# gps_and_sensor_board.net
KiCad netlist of a schematic drawn in EAGLE
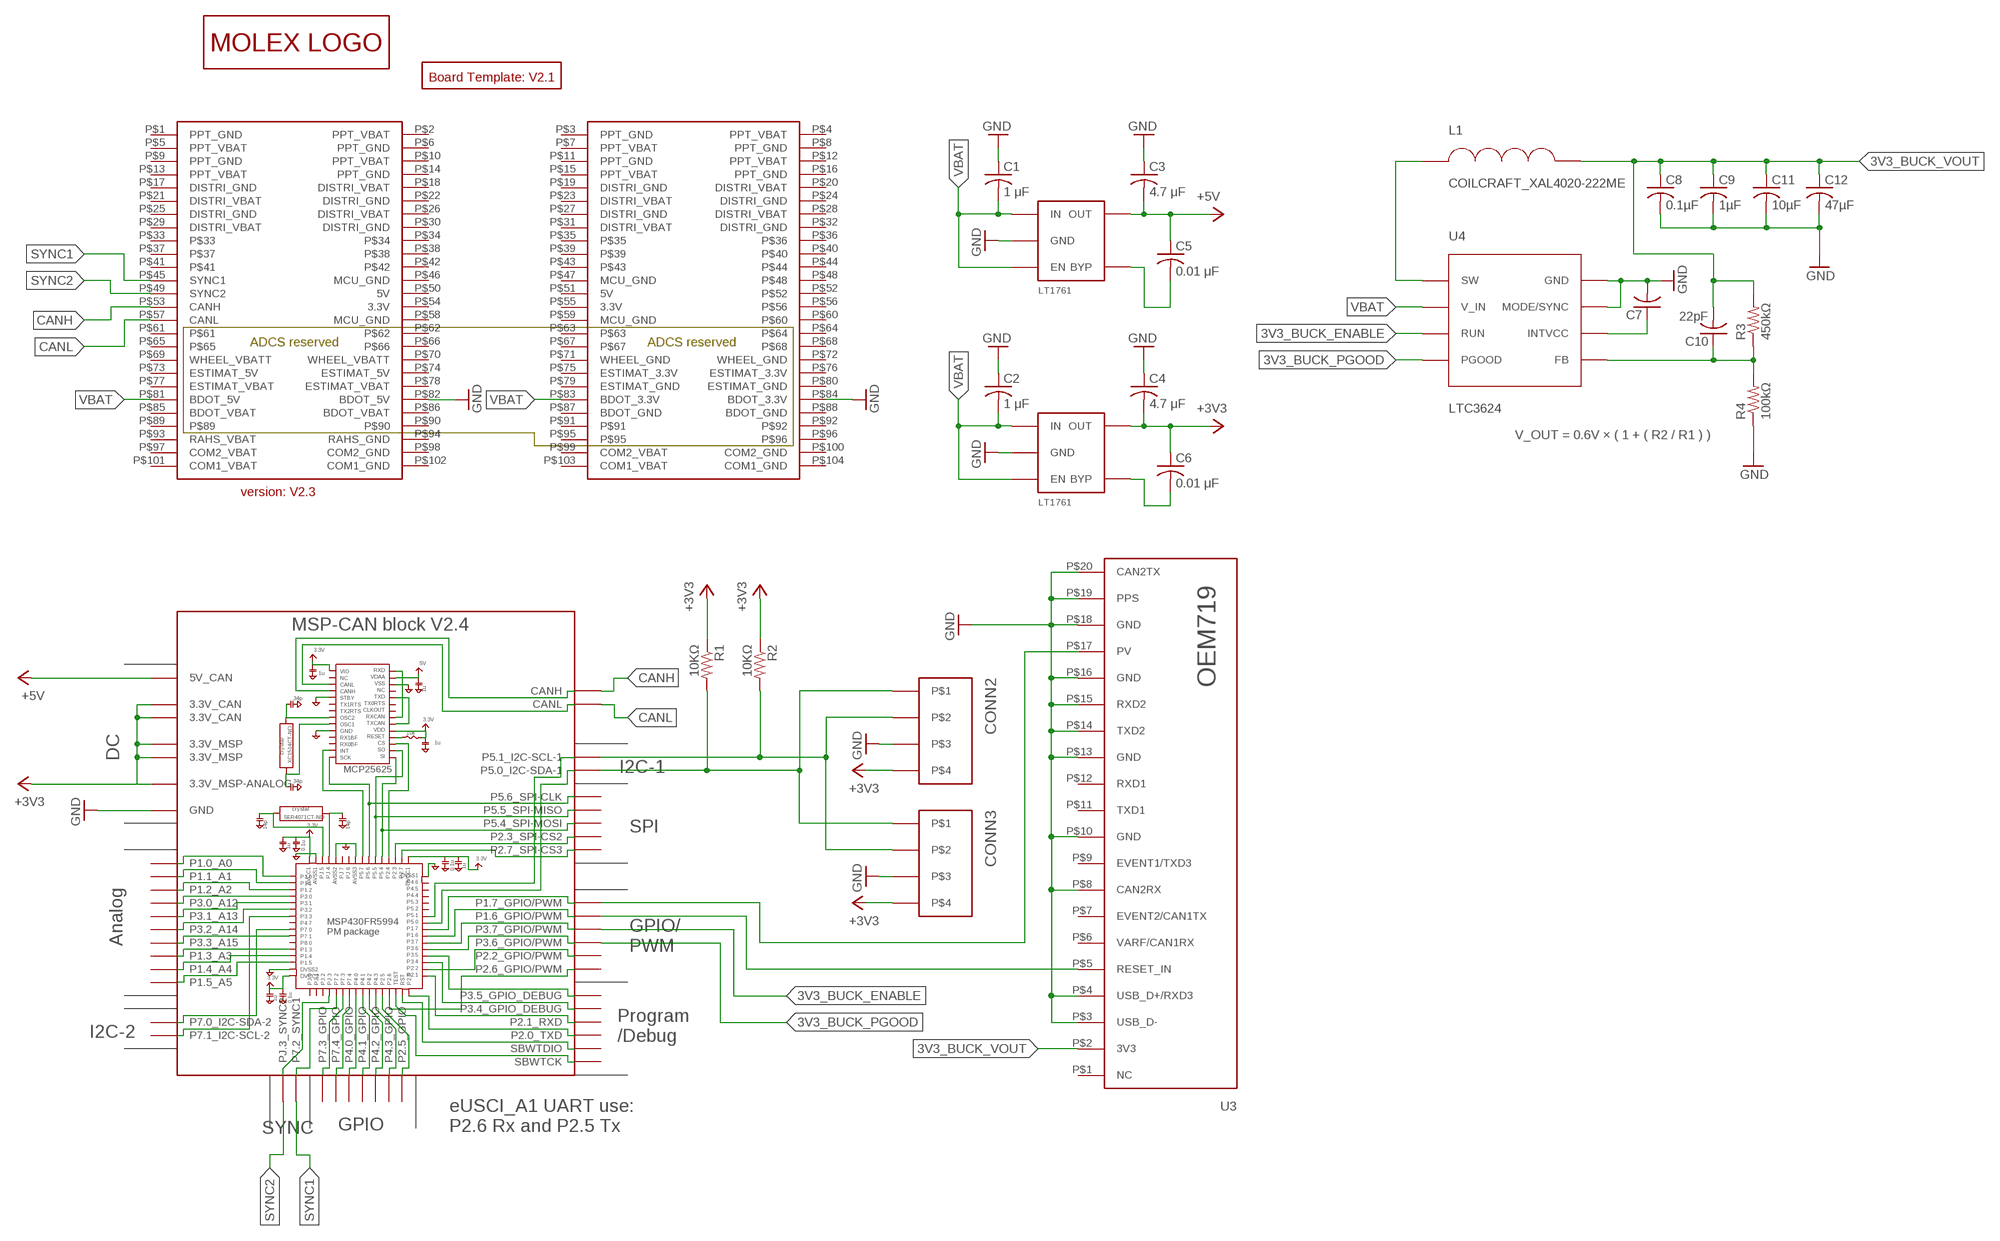
[diagram p0: schematic, sheet 1]

(export (version "E")
  (design (tool "Eeschema 10.0.6"))
  (components
    (comp (ref "B1")
      (value "BOARD_TEMPLATE1")
      (footprint "eagle-import:BOARD_TEMPLATE")
      (libsource (lib "eagle-import") (part "BOARD_TEMPLATE1"))
    )
    (comp (ref "BLK1")
      (value "MSP-CAN_BLOCK")
      (footprint "eagle-import:MSP-CAN_BLOCK")
      (libsource (lib "eagle-import") (part "MSP-CAN_BLOCK"))
    )
    (comp (ref "C1")
      (value "1 μF")
      (footprint "eagle-import:C0805")
      (libsource (lib "eagle-import") (part "C-USC0805"))
    )
    (comp (ref "C2")
      (value "1 μF")
      (footprint "eagle-import:C0805")
      (libsource (lib "eagle-import") (part "C-USC0805"))
    )
    (comp (ref "C3")
      (value "4.7 μF")
      (footprint "eagle-import:C0805")
      (libsource (lib "eagle-import") (part "C-USC0805"))
    )
    (comp (ref "C4")
      (value "4.7 μF")
      (footprint "eagle-import:C0805")
      (libsource (lib "eagle-import") (part "C-USC0805"))
    )
    (comp (ref "C5")
      (value "0.01 μF")
      (footprint "eagle-import:C0805")
      (libsource (lib "eagle-import") (part "C-USC0805"))
    )
    (comp (ref "C6")
      (value "0.01 μF")
      (footprint "eagle-import:C0805")
      (libsource (lib "eagle-import") (part "C-USC0805"))
    )
    (comp (ref "C7")
      (value "C-USC0805")
      (footprint "eagle-import:C0805")
      (libsource (lib "eagle-import") (part "C-USC0805"))
    )
    (comp (ref "C8")
      (value "0.1µF")
      (footprint "eagle-import:C1206")
      (libsource (lib "eagle-import") (part "C-USC1206"))
    )
    (comp (ref "C9")
      (value "1µF")
      (footprint "eagle-import:C0805")
      (libsource (lib "eagle-import") (part "C-USC0805"))
    )
    (comp (ref "C10")
      (value "22pF")
      (footprint "eagle-import:C0805")
      (libsource (lib "eagle-import") (part "C-USC0805"))
    )
    (comp (ref "C11")
      (value "10µF")
      (footprint "eagle-import:C0805")
      (libsource (lib "eagle-import") (part "C-USC0805"))
    )
    (comp (ref "C12")
      (value "47µF")
      (footprint "eagle-import:C0805")
      (libsource (lib "eagle-import") (part "C-USC0805"))
    )
    (comp (ref "CONN1")
      (value "PC104_CONNECTOR")
      (footprint "eagle-import:PC104_CONNECTOR")
      (libsource (lib "eagle-import") (part "PC104_CONNECTOR"))
    )
    (comp (ref "CONN2")
      (value "PICOLOCK_4")
      (footprint "eagle-import:PICOLOCK_4")
      (libsource (lib "eagle-import") (part "PICOLOCK_4"))
    )
    (comp (ref "CONN3")
      (value "PICOLOCK_4")
      (footprint "eagle-import:PICOLOCK_4")
      (libsource (lib "eagle-import") (part "PICOLOCK_4"))
    )
    (comp (ref "L1")
      (value "COILCRAFT_XAL4020-222ME")
      (footprint "eagle-import:COILCRAFT_XAL4020")
      (libsource (lib "eagle-import") (part "COILCRAFT_XAL4020-222ME"))
    )
    (comp (ref "R1")
      (value "10KΩ")
      (footprint "eagle-import:R0805")
      (libsource (lib "eagle-import") (part "R-US_R0805"))
    )
    (comp (ref "R2")
      (value "10KΩ")
      (footprint "eagle-import:R0805")
      (libsource (lib "eagle-import") (part "R-US_R0805"))
    )
    (comp (ref "R3")
      (value "450kΩ")
      (footprint "eagle-import:R0805")
      (libsource (lib "eagle-import") (part "R-US_R0805"))
    )
    (comp (ref "R4")
      (value "100kΩ")
      (footprint "eagle-import:R0805")
      (libsource (lib "eagle-import") (part "R-US_R0805"))
    )
    (comp (ref "U$1")
      (value "LOGO_MOLEX")
      (footprint "eagle-import:LOGO_MOLEX")
      (libsource (lib "eagle-import") (part "LOGO_MOLEX"))
    )
    (comp (ref "U1")
      (value "LINEAR_LDO_LT1761-X")
      (footprint "eagle-import:SOT-23-5")
      (libsource (lib "eagle-import") (part "LINEAR_LDO_LT1761-X"))
    )
    (comp (ref "U2")
      (value "LINEAR_LDO_LT1761-X")
      (footprint "eagle-import:SOT-23-5")
      (libsource (lib "eagle-import") (part "LINEAR_LDO_LT1761-X"))
    )
    (comp (ref "U3")
      (value "OEM719")
      (footprint "eagle-import:OEM719")
      (libsource (lib "eagle-import") (part "OEM719"))
    )
    (comp (ref "U4")
      (value "LTC3624")
      (footprint "eagle-import:LTC3624")
      (libsource (lib "eagle-import") (part "LTC3624"))
    )
  )
  (nets
    (net (code "1") (name "+3V3") (class "Default")
      (node (ref "BLK1") (pin "3.3V@CAN1") (pinfunction "3.3V_CAN_3.3V@CAN1") (pintype "bidirectional"))
      (node (ref "BLK1") (pin "3.3V@CAN2") (pinfunction "3.3V_CAN_3.3V@CAN2") (pintype "bidirectional"))
      (node (ref "BLK1") (pin "3.3V@MSP1") (pinfunction "3.3V_MSP_3.3V@MSP1") (pintype "bidirectional"))
      (node (ref "BLK1") (pin "3.3V@MSP2") (pinfunction "3.3V_MSP_3.3V@MSP2") (pintype "bidirectional"))
      (node (ref "BLK1") (pin "3.3V_ANALOG@MSP2") (pinfunction "3.3V_MSP-ANALOG_3.3V_ANALOG@MSP2") (pintype "bidirectional"))
      (node (ref "C4") (pin "2") (pinfunction "2_2") (pintype "passive"))
      (node (ref "C6") (pin "1") (pinfunction "1_1") (pintype "passive"))
      (node (ref "CONN2") (pin "P$4") (pinfunction "P$4_P$4") (pintype "bidirectional"))
      (node (ref "CONN3") (pin "P$4") (pinfunction "P$4_P$4") (pintype "bidirectional"))
      (node (ref "R1") (pin "1") (pinfunction "1_1") (pintype "passive"))
      (node (ref "R2") (pin "1") (pinfunction "1_1") (pintype "passive"))
      (node (ref "U2") (pin "P$5") (pinfunction "OUT_P$5") (pintype "bidirectional"))
    )
    (net (code "2") (name "+5V") (class "Default")
      (node (ref "BLK1") (pin "5V") (pinfunction "5V_CAN_5V") (pintype "bidirectional"))
      (node (ref "C3") (pin "2") (pinfunction "2_2") (pintype "passive"))
      (node (ref "C5") (pin "1") (pinfunction "1_1") (pintype "passive"))
      (node (ref "U1") (pin "P$5") (pinfunction "OUT_P$5") (pintype "bidirectional"))
    )
    (net (code "3") (name "3V3_BUCK_ENABLE") (class "Default")
      (node (ref "BLK1") (pin "P3.7_GPIO/PWM") (pinfunction "P3.7_GPIO/PWM_P3.7_GPIO/PWM") (pintype "bidirectional"))
      (node (ref "U4") (pin "RUN") (pinfunction "RUN_RUN") (pintype "bidirectional"))
    )
    (net (code "4") (name "3V3_BUCK_PGOOD") (class "Default")
      (node (ref "BLK1") (pin "P3.6_GPIO/PWM") (pinfunction "P3.6_GPIO/PWM_P3.6_GPIO/PWM") (pintype "bidirectional"))
      (node (ref "U4") (pin "PGOOD") (pinfunction "PGOOD_PGOOD") (pintype "bidirectional"))
    )
    (net (code "5") (name "3V3_BUCK_VOUT") (class "Default")
      (node (ref "C10") (pin "2") (pinfunction "2_2") (pintype "passive"))
      (node (ref "C11") (pin "1") (pinfunction "1_1") (pintype "passive"))
      (node (ref "C12") (pin "1") (pinfunction "1_1") (pintype "passive"))
      (node (ref "C8") (pin "1") (pinfunction "1_1") (pintype "passive"))
      (node (ref "C9") (pin "1") (pinfunction "1_1") (pintype "passive"))
      (node (ref "L1") (pin "P$2") (pinfunction "P$2_P$2") (pintype "bidirectional"))
      (node (ref "R3") (pin "2") (pinfunction "2_2") (pintype "passive"))
      (node (ref "U3") (pin "P$2") (pinfunction "3V3_P$2") (pintype "bidirectional"))
    )
    (net (code "6") (name "CANH") (class "Default")
      (node (ref "BLK1") (pin "CANH") (pinfunction "CANH_CANH") (pintype "bidirectional"))
      (node (ref "CONN1") (pin "P$53") (pinfunction "CANH_P$53") (pintype "bidirectional"))
    )
    (net (code "7") (name "CANL") (class "Default")
      (node (ref "BLK1") (pin "CANL") (pinfunction "CANL_CANL") (pintype "bidirectional"))
      (node (ref "CONN1") (pin "P$57") (pinfunction "CANL_P$57") (pintype "bidirectional"))
    )
    (net (code "8") (name "GND") (class "Default")
      (node (ref "BLK1") (pin "GND@1") (pinfunction "GND_GND@1") (pintype "bidirectional"))
      (node (ref "BLK1") (pin "GND@10") (pinfunction "GND_GND@10") (pintype "bidirectional"))
      (node (ref "BLK1") (pin "GND@11") (pinfunction "GND_GND@11") (pintype "bidirectional"))
      (node (ref "BLK1") (pin "GND@12") (pinfunction "GND_GND@12") (pintype "bidirectional"))
      (node (ref "BLK1") (pin "GND@13") (pinfunction "GND_GND@13") (pintype "bidirectional"))
      (node (ref "BLK1") (pin "GND@14") (pinfunction "GND_GND@14") (pintype "bidirectional"))
      (node (ref "BLK1") (pin "GND@15") (pinfunction "GND_GND@15") (pintype "bidirectional"))
      (node (ref "BLK1") (pin "GND@16") (pinfunction "GND_GND@16") (pintype "bidirectional"))
      (node (ref "BLK1") (pin "GND@17") (pinfunction "GND_GND@17") (pintype "bidirectional"))
      (node (ref "BLK1") (pin "GND@2") (pinfunction "GND_GND@2") (pintype "bidirectional"))
      (node (ref "BLK1") (pin "GND@26") (pinfunction "GND_GND@26") (pintype "bidirectional"))
      (node (ref "BLK1") (pin "GND@3") (pinfunction "GND_GND@3") (pintype "bidirectional"))
      (node (ref "BLK1") (pin "GND@4") (pinfunction "GND_GND@4") (pintype "bidirectional"))
      (node (ref "BLK1") (pin "GND@5") (pinfunction "GND_GND@5") (pintype "bidirectional"))
      (node (ref "BLK1") (pin "GND@7") (pinfunction "GND_GND@7") (pintype "bidirectional"))
      (node (ref "BLK1") (pin "GND@8") (pinfunction "GND_GND@8") (pintype "bidirectional"))
      (node (ref "BLK1") (pin "GND@9") (pinfunction "GND_GND@9") (pintype "bidirectional"))
      (node (ref "C1") (pin "1") (pinfunction "1_1") (pintype "passive"))
      (node (ref "C11") (pin "2") (pinfunction "2_2") (pintype "passive"))
      (node (ref "C12") (pin "2") (pinfunction "2_2") (pintype "passive"))
      (node (ref "C2") (pin "1") (pinfunction "1_1") (pintype "passive"))
      (node (ref "C3") (pin "1") (pinfunction "1_1") (pintype "passive"))
      (node (ref "C4") (pin "1") (pinfunction "1_1") (pintype "passive"))
      (node (ref "C7") (pin "2") (pinfunction "2_2") (pintype "passive"))
      (node (ref "C8") (pin "2") (pinfunction "2_2") (pintype "passive"))
      (node (ref "C9") (pin "2") (pinfunction "2_2") (pintype "passive"))
      (node (ref "CONN1") (pin "P$82") (pinfunction "BDOT_5V_P$82") (pintype "bidirectional"))
      (node (ref "CONN1") (pin "P$84") (pinfunction "BDOT_3.3V_P$84") (pintype "bidirectional"))
      (node (ref "CONN2") (pin "P$3") (pinfunction "P$3_P$3") (pintype "bidirectional"))
      (node (ref "CONN3") (pin "P$3") (pinfunction "P$3_P$3") (pintype "bidirectional"))
      (node (ref "R4") (pin "1") (pinfunction "1_1") (pintype "passive"))
      (node (ref "U1") (pin "P$2") (pinfunction "GND_P$2") (pintype "bidirectional"))
      (node (ref "U2") (pin "P$2") (pinfunction "GND_P$2") (pintype "bidirectional"))
      (node (ref "U3") (pin "P$10") (pinfunction "GND_P$10") (pintype "bidirectional"))
      (node (ref "U3") (pin "P$13") (pinfunction "GND_P$13") (pintype "bidirectional"))
      (node (ref "U3") (pin "P$14") (pinfunction "TXD2_P$14") (pintype "bidirectional"))
      (node (ref "U3") (pin "P$15") (pinfunction "RXD2_P$15") (pintype "bidirectional"))
      (node (ref "U3") (pin "P$16") (pinfunction "GND_P$16") (pintype "bidirectional"))
      (node (ref "U3") (pin "P$18") (pinfunction "GND_P$18") (pintype "bidirectional"))
      (node (ref "U3") (pin "P$19") (pinfunction "PPS_P$19") (pintype "bidirectional"))
      (node (ref "U3") (pin "P$20") (pinfunction "CAN2TX_P$20") (pintype "bidirectional"))
      (node (ref "U3") (pin "P$3") (pinfunction "USB_D-_P$3") (pintype "bidirectional"))
      (node (ref "U3") (pin "P$4") (pinfunction "USB_D+/RXD3_P$4") (pintype "bidirectional"))
      (node (ref "U3") (pin "P$8") (pinfunction "CAN2RX_P$8") (pintype "bidirectional"))
      (node (ref "U4") (pin "GND@1") (pinfunction "GND_GND@1") (pintype "bidirectional"))
      (node (ref "U4") (pin "GND@PAD") (pinfunction "GND_GND@PAD") (pintype "bidirectional"))
      (node (ref "U4") (pin "MODE/SYNC") (pinfunction "MODE/SYNC_MODE/SYNC") (pintype "bidirectional"))
    )
    (net (code "9") (name "Net-(BLK1-PadP5.0_I2C-SDA-1)") (class "Default")
      (node (ref "BLK1") (pin "P5.0_I2C-SDA-1") (pinfunction "P5.0_I2C-SDA-1_P5.0_I2C-SDA-1") (pintype "bidirectional"))
      (node (ref "CONN2") (pin "P$1") (pinfunction "P$1_P$1") (pintype "bidirectional"))
      (node (ref "CONN3") (pin "P$1") (pinfunction "P$1_P$1") (pintype "bidirectional"))
      (node (ref "R1") (pin "2") (pinfunction "2_2") (pintype "passive"))
    )
    (net (code "10") (name "Net-(BLK1-PadP5.1_I2C-SCL-1)") (class "Default")
      (node (ref "BLK1") (pin "P5.1_I2C-SCL-1") (pinfunction "P5.1_I2C-SCL-1_P5.1_I2C-SCL-1") (pintype "bidirectional"))
      (node (ref "CONN2") (pin "P$2") (pinfunction "P$2_P$2") (pintype "bidirectional"))
      (node (ref "CONN3") (pin "P$2") (pinfunction "P$2_P$2") (pintype "bidirectional"))
      (node (ref "R2") (pin "2") (pinfunction "2_2") (pintype "passive"))
    )
    (net (code "11") (name "Net-(C7-Pad1)") (class "Default")
      (node (ref "C7") (pin "1") (pinfunction "1_1") (pintype "passive"))
      (node (ref "U4") (pin "INTVCC") (pinfunction "INTVCC_INTVCC") (pintype "bidirectional"))
    )
    (net (code "12") (name "Net-(C10-Pad1)") (class "Default")
      (node (ref "C10") (pin "1") (pinfunction "1_1") (pintype "passive"))
      (node (ref "R3") (pin "1") (pinfunction "1_1") (pintype "passive"))
      (node (ref "R4") (pin "2") (pinfunction "2_2") (pintype "passive"))
      (node (ref "U4") (pin "FB") (pinfunction "FB_FB") (pintype "bidirectional"))
    )
    (net (code "13") (name "Net-(L1-PadP$1)") (class "Default")
      (node (ref "L1") (pin "P$1") (pinfunction "P$1_P$1") (pintype "bidirectional"))
      (node (ref "U4") (pin "SW") (pinfunction "SW_SW") (pintype "bidirectional"))
    )
    (net (code "14") (name "Net-(U1-BYP)") (class "Default")
      (node (ref "C5") (pin "2") (pinfunction "2_2") (pintype "passive"))
      (node (ref "U1") (pin "P$4") (pinfunction "BYP_P$4") (pintype "bidirectional"))
    )
    (net (code "15") (name "Net-(U2-BYP)") (class "Default")
      (node (ref "C6") (pin "2") (pinfunction "2_2") (pintype "passive"))
      (node (ref "U2") (pin "P$4") (pinfunction "BYP_P$4") (pintype "bidirectional"))
    )
    (net (code "16") (name "Net-(U3-PV)") (class "Default")
      (node (ref "BLK1") (pin "P1.7_GPIO/PWM") (pinfunction "P1.7_GPIO/PWM_P1.7_GPIO/PWM") (pintype "bidirectional"))
      (node (ref "U3") (pin "P$17") (pinfunction "PV_P$17") (pintype "bidirectional"))
    )
    (net (code "17") (name "Net-(U3-RESET_IN)") (class "Default")
      (node (ref "BLK1") (pin "P1.6_GPIO/PWM") (pinfunction "P1.6_GPIO/PWM_P1.6_GPIO/PWM") (pintype "bidirectional"))
      (node (ref "U3") (pin "P$5") (pinfunction "RESET_IN_P$5") (pintype "bidirectional"))
    )
    (net (code "18") (name "SYNC1") (class "Default")
      (node (ref "BLK1") (pin "P7.2_SYNC1") (pinfunction "P7.2_SYNC1_P7.2_SYNC1") (pintype "bidirectional"))
      (node (ref "CONN1") (pin "P$45") (pinfunction "SYNC1_P$45") (pintype "bidirectional"))
    )
    (net (code "19") (name "SYNC2") (class "Default")
      (node (ref "BLK1") (pin "PJ.3_SYNC2") (pinfunction "PJ.3_SYNC2_PJ.3_SYNC2") (pintype "bidirectional"))
      (node (ref "CONN1") (pin "P$49") (pinfunction "SYNC2_P$49") (pintype "bidirectional"))
    )
    (net (code "20") (name "VBAT") (class "Default")
      (node (ref "C1") (pin "2") (pinfunction "2_2") (pintype "passive"))
      (node (ref "C2") (pin "2") (pinfunction "2_2") (pintype "passive"))
      (node (ref "CONN1") (pin "P$81") (pinfunction "BDOT_5V_P$81") (pintype "bidirectional"))
      (node (ref "CONN1") (pin "P$83") (pinfunction "BDOT_3.3V_P$83") (pintype "bidirectional"))
      (node (ref "U1") (pin "P$1") (pinfunction "IN_P$1") (pintype "bidirectional"))
      (node (ref "U1") (pin "P$3") (pinfunction "EN_P$3") (pintype "bidirectional"))
      (node (ref "U2") (pin "P$1") (pinfunction "IN_P$1") (pintype "bidirectional"))
      (node (ref "U2") (pin "P$3") (pinfunction "EN_P$3") (pintype "bidirectional"))
      (node (ref "U4") (pin "V_IN") (pinfunction "V_IN_V_IN") (pintype "bidirectional"))
    )
    (net (code "21") (name "unconnected-(BLK1-P2.3_SPI-CS2-PadP2.4_SPI-CS2)") (class "Default")
      (node (ref "BLK1") (pin "P2.4_SPI-CS2") (pinfunction "P2.3_SPI-CS2_P2.4_SPI-CS2") (pintype "bidirectional"))
    )
    (net (code "22") (name "unconnected-(BLK1-PadP1.0_A0)") (class "Default")
      (node (ref "BLK1") (pin "P1.0_A0") (pinfunction "P1.0_A0_P1.0_A0") (pintype "bidirectional"))
    )
    (net (code "23") (name "unconnected-(BLK1-PadP1.1_A1)") (class "Default")
      (node (ref "BLK1") (pin "P1.1_A1") (pinfunction "P1.1_A1_P1.1_A1") (pintype "bidirectional"))
    )
    (net (code "24") (name "unconnected-(BLK1-PadP1.2_A2)") (class "Default")
      (node (ref "BLK1") (pin "P1.2_A2") (pinfunction "P1.2_A2_P1.2_A2") (pintype "bidirectional"))
    )
    (net (code "25") (name "unconnected-(BLK1-PadP1.3_A3)") (class "Default")
      (node (ref "BLK1") (pin "P1.3_A3") (pinfunction "P1.3_A3_P1.3_A3") (pintype "bidirectional"))
    )
    (net (code "26") (name "unconnected-(BLK1-PadP1.4_A4)") (class "Default")
      (node (ref "BLK1") (pin "P1.4_A4") (pinfunction "P1.4_A4_P1.4_A4") (pintype "bidirectional"))
    )
    (net (code "27") (name "unconnected-(BLK1-PadP1.5_A5)") (class "Default")
      (node (ref "BLK1") (pin "P1.5_A5") (pinfunction "P1.5_A5_P1.5_A5") (pintype "bidirectional"))
    )
    (net (code "28") (name "unconnected-(BLK1-PadP2.0_TXD)") (class "Default")
      (node (ref "BLK1") (pin "P2.0_TXD") (pinfunction "P2.0_TXD_P2.0_TXD") (pintype "bidirectional"))
    )
    (net (code "29") (name "unconnected-(BLK1-PadP2.1_RXD)") (class "Default")
      (node (ref "BLK1") (pin "P2.1_RXD") (pinfunction "P2.1_RXD_P2.1_RXD") (pintype "bidirectional"))
    )
    (net (code "30") (name "unconnected-(BLK1-PadP2.2_GPIO{slash}PWM)") (class "Default")
      (node (ref "BLK1") (pin "P2.2_GPIO/PWM") (pinfunction "P2.2_GPIO/PWM_P2.2_GPIO/PWM") (pintype "bidirectional"))
    )
    (net (code "31") (name "unconnected-(BLK1-PadP2.5_GPIO)") (class "Default")
      (node (ref "BLK1") (pin "P2.5_GPIO") (pinfunction "P2.5_GPIO_P2.5_GPIO") (pintype "bidirectional"))
    )
    (net (code "32") (name "unconnected-(BLK1-PadP2.6_GPIO{slash}PWM)") (class "Default")
      (node (ref "BLK1") (pin "P2.6_GPIO/PWM") (pinfunction "P2.6_GPIO/PWM_P2.6_GPIO/PWM") (pintype "bidirectional"))
    )
    (net (code "33") (name "unconnected-(BLK1-PadP2.7_SPI-CS3)") (class "Default")
      (node (ref "BLK1") (pin "P2.7_SPI-CS3") (pinfunction "P2.7_SPI-CS3_P2.7_SPI-CS3") (pintype "bidirectional"))
    )
    (net (code "34") (name "unconnected-(BLK1-PadP3.0_A12)") (class "Default")
      (node (ref "BLK1") (pin "P3.0_A12") (pinfunction "P3.0_A12_P3.0_A12") (pintype "bidirectional"))
    )
    (net (code "35") (name "unconnected-(BLK1-PadP3.1_A13)") (class "Default")
      (node (ref "BLK1") (pin "P3.1_A13") (pinfunction "P3.1_A13_P3.1_A13") (pintype "bidirectional"))
    )
    (net (code "36") (name "unconnected-(BLK1-PadP3.2_A14)") (class "Default")
      (node (ref "BLK1") (pin "P3.2_A14") (pinfunction "P3.2_A14_P3.2_A14") (pintype "bidirectional"))
    )
    (net (code "37") (name "unconnected-(BLK1-PadP3.3_A15)") (class "Default")
      (node (ref "BLK1") (pin "P3.3_A15") (pinfunction "P3.3_A15_P3.3_A15") (pintype "bidirectional"))
    )
    (net (code "38") (name "unconnected-(BLK1-PadP3.4_GPIO_DEBUG)") (class "Default")
      (node (ref "BLK1") (pin "P3.4_GPIO_DEBUG") (pinfunction "P3.4_GPIO_DEBUG_P3.4_GPIO_DEBUG") (pintype "bidirectional"))
    )
    (net (code "39") (name "unconnected-(BLK1-PadP3.5_GPIO_DEBUG)") (class "Default")
      (node (ref "BLK1") (pin "P3.5_GPIO_DEBUG") (pinfunction "P3.5_GPIO_DEBUG_P3.5_GPIO_DEBUG") (pintype "bidirectional"))
    )
    (net (code "40") (name "unconnected-(BLK1-PadP4.0_GPIO)") (class "Default")
      (node (ref "BLK1") (pin "P4.0_GPIO") (pinfunction "P4.0_GPIO_P4.0_GPIO") (pintype "bidirectional"))
    )
    (net (code "41") (name "unconnected-(BLK1-PadP4.1_GPIO)") (class "Default")
      (node (ref "BLK1") (pin "P4.1_GPIO") (pinfunction "P4.1_GPIO_P4.1_GPIO") (pintype "bidirectional"))
    )
    (net (code "42") (name "unconnected-(BLK1-PadP4.2_GPIO)") (class "Default")
      (node (ref "BLK1") (pin "P4.2_GPIO") (pinfunction "P4.2_GPIO_P4.2_GPIO") (pintype "bidirectional"))
    )
    (net (code "43") (name "unconnected-(BLK1-PadP4.3_GPIO)") (class "Default")
      (node (ref "BLK1") (pin "P4.3_GPIO") (pinfunction "P4.3_GPIO_P4.3_GPIO") (pintype "bidirectional"))
    )
    (net (code "44") (name "unconnected-(BLK1-PadP5.4_SPI-MOSI)") (class "Default")
      (node (ref "BLK1") (pin "P5.4_SPI-MOSI") (pinfunction "P5.4_SPI-MOSI_P5.4_SPI-MOSI") (pintype "bidirectional"))
    )
    (net (code "45") (name "unconnected-(BLK1-PadP5.5_SPI-MISO)") (class "Default")
      (node (ref "BLK1") (pin "P5.5_SPI-MISO") (pinfunction "P5.5_SPI-MISO_P5.5_SPI-MISO") (pintype "bidirectional"))
    )
    (net (code "46") (name "unconnected-(BLK1-PadP5.6_SPI-CLK)") (class "Default")
      (node (ref "BLK1") (pin "P5.6_SPI-CLK") (pinfunction "P5.6_SPI-CLK_P5.6_SPI-CLK") (pintype "bidirectional"))
    )
    (net (code "47") (name "unconnected-(BLK1-PadP7.0_I2C-SDA-2)") (class "Default")
      (node (ref "BLK1") (pin "P7.0_I2C-SDA-2") (pinfunction "P7.0_I2C-SDA-2_P7.0_I2C-SDA-2") (pintype "bidirectional"))
    )
    (net (code "48") (name "unconnected-(BLK1-PadP7.1_I2C-SCL-2)") (class "Default")
      (node (ref "BLK1") (pin "P7.1_I2C-SCL-2") (pinfunction "P7.1_I2C-SCL-2_P7.1_I2C-SCL-2") (pintype "bidirectional"))
    )
    (net (code "49") (name "unconnected-(BLK1-PadP7.3_GPIO)") (class "Default")
      (node (ref "BLK1") (pin "P7.3_GPIO") (pinfunction "P7.3_GPIO_P7.3_GPIO") (pintype "bidirectional"))
    )
    (net (code "50") (name "unconnected-(BLK1-PadP7.4_GPIO)") (class "Default")
      (node (ref "BLK1") (pin "P7.4_GPIO") (pinfunction "P7.4_GPIO_P7.4_GPIO") (pintype "bidirectional"))
    )
    (net (code "51") (name "unconnected-(BLK1-PadSBWTCK)") (class "Default")
      (node (ref "BLK1") (pin "SBWTCK") (pinfunction "SBWTCK_SBWTCK") (pintype "bidirectional"))
    )
    (net (code "52") (name "unconnected-(BLK1-PadSBWTDIO)") (class "Default")
      (node (ref "BLK1") (pin "SBWTDIO") (pinfunction "SBWTDIO_SBWTDIO") (pintype "bidirectional"))
    )
    (net (code "53") (name "unconnected-(CONN1-3.3V-PadP$54)") (class "Default")
      (node (ref "CONN1") (pin "P$54") (pinfunction "3.3V_P$54") (pintype "bidirectional"))
    )
    (net (code "54") (name "unconnected-(CONN1-3.3V-PadP$55)") (class "Default")
      (node (ref "CONN1") (pin "P$55") (pinfunction "3.3V_P$55") (pintype "bidirectional"))
    )
    (net (code "55") (name "unconnected-(CONN1-5V-PadP$50)") (class "Default")
      (node (ref "CONN1") (pin "P$50") (pinfunction "5V_P$50") (pintype "bidirectional"))
    )
    (net (code "56") (name "unconnected-(CONN1-5V-PadP$51)") (class "Default")
      (node (ref "CONN1") (pin "P$51") (pinfunction "5V_P$51") (pintype "bidirectional"))
    )
    (net (code "57") (name "unconnected-(CONN1-BDOT_GND-PadP$87)") (class "Default")
      (node (ref "CONN1") (pin "P$87") (pinfunction "BDOT_GND_P$87") (pintype "bidirectional"))
    )
    (net (code "58") (name "unconnected-(CONN1-BDOT_GND-PadP$88)") (class "Default")
      (node (ref "CONN1") (pin "P$88") (pinfunction "BDOT_GND_P$88") (pintype "bidirectional"))
    )
    (net (code "59") (name "unconnected-(CONN1-BDOT_VBAT-PadP$85)") (class "Default")
      (node (ref "CONN1") (pin "P$85") (pinfunction "BDOT_VBAT_P$85") (pintype "bidirectional"))
    )
    (net (code "60") (name "unconnected-(CONN1-BDOT_VBAT-PadP$86)") (class "Default")
      (node (ref "CONN1") (pin "P$86") (pinfunction "BDOT_VBAT_P$86") (pintype "bidirectional"))
    )
    (net (code "61") (name "unconnected-(CONN1-COM1_GND-PadP$102)") (class "Default")
      (node (ref "CONN1") (pin "P$102") (pinfunction "COM1_GND_P$102") (pintype "bidirectional"))
    )
    (net (code "62") (name "unconnected-(CONN1-COM1_GND-PadP$104)") (class "Default")
      (node (ref "CONN1") (pin "P$104") (pinfunction "COM1_GND_P$104") (pintype "bidirectional"))
    )
    (net (code "63") (name "unconnected-(CONN1-COM1_VBAT-PadP$101)") (class "Default")
      (node (ref "CONN1") (pin "P$101") (pinfunction "COM1_VBAT_P$101") (pintype "bidirectional"))
    )
    (net (code "64") (name "unconnected-(CONN1-COM1_VBAT-PadP$103)") (class "Default")
      (node (ref "CONN1") (pin "P$103") (pinfunction "COM1_VBAT_P$103") (pintype "bidirectional"))
    )
    (net (code "65") (name "unconnected-(CONN1-COM2_GND-PadP$98)") (class "Default")
      (node (ref "CONN1") (pin "P$98") (pinfunction "COM2_GND_P$98") (pintype "bidirectional"))
    )
    (net (code "66") (name "unconnected-(CONN1-COM2_GND-PadP$100)") (class "Default")
      (node (ref "CONN1") (pin "P$100") (pinfunction "COM2_GND_P$100") (pintype "bidirectional"))
    )
    (net (code "67") (name "unconnected-(CONN1-COM2_VBAT-PadP$97)") (class "Default")
      (node (ref "CONN1") (pin "P$97") (pinfunction "COM2_VBAT_P$97") (pintype "bidirectional"))
    )
    (net (code "68") (name "unconnected-(CONN1-COM2_VBAT-PadP$99)") (class "Default")
      (node (ref "CONN1") (pin "P$99") (pinfunction "COM2_VBAT_P$99") (pintype "bidirectional"))
    )
    (net (code "69") (name "unconnected-(CONN1-DISTRI_GND-PadP$17)") (class "Default")
      (node (ref "CONN1") (pin "P$17") (pinfunction "DISTRI_GND_P$17") (pintype "bidirectional"))
    )
    (net (code "70") (name "unconnected-(CONN1-DISTRI_GND-PadP$19)") (class "Default")
      (node (ref "CONN1") (pin "P$19") (pinfunction "DISTRI_GND_P$19") (pintype "bidirectional"))
    )
    (net (code "71") (name "unconnected-(CONN1-DISTRI_GND-PadP$22)") (class "Default")
      (node (ref "CONN1") (pin "P$22") (pinfunction "DISTRI_GND_P$22") (pintype "bidirectional"))
    )
    (net (code "72") (name "unconnected-(CONN1-DISTRI_GND-PadP$24)") (class "Default")
      (node (ref "CONN1") (pin "P$24") (pinfunction "DISTRI_GND_P$24") (pintype "bidirectional"))
    )
    (net (code "73") (name "unconnected-(CONN1-DISTRI_GND-PadP$25)") (class "Default")
      (node (ref "CONN1") (pin "P$25") (pinfunction "DISTRI_GND_P$25") (pintype "bidirectional"))
    )
    (net (code "74") (name "unconnected-(CONN1-DISTRI_GND-PadP$27)") (class "Default")
      (node (ref "CONN1") (pin "P$27") (pinfunction "DISTRI_GND_P$27") (pintype "bidirectional"))
    )
    (net (code "75") (name "unconnected-(CONN1-DISTRI_GND-PadP$30)") (class "Default")
      (node (ref "CONN1") (pin "P$30") (pinfunction "DISTRI_GND_P$30") (pintype "bidirectional"))
    )
    (net (code "76") (name "unconnected-(CONN1-DISTRI_GND-PadP$32)") (class "Default")
      (node (ref "CONN1") (pin "P$32") (pinfunction "DISTRI_GND_P$32") (pintype "bidirectional"))
    )
    (net (code "77") (name "unconnected-(CONN1-DISTRI_VBAT-PadP$18)") (class "Default")
      (node (ref "CONN1") (pin "P$18") (pinfunction "DISTRI_VBAT_P$18") (pintype "bidirectional"))
    )
    (net (code "78") (name "unconnected-(CONN1-DISTRI_VBAT-PadP$20)") (class "Default")
      (node (ref "CONN1") (pin "P$20") (pinfunction "DISTRI_VBAT_P$20") (pintype "bidirectional"))
    )
    (net (code "79") (name "unconnected-(CONN1-DISTRI_VBAT-PadP$21)") (class "Default")
      (node (ref "CONN1") (pin "P$21") (pinfunction "DISTRI_VBAT_P$21") (pintype "bidirectional"))
    )
    (net (code "80") (name "unconnected-(CONN1-DISTRI_VBAT-PadP$23)") (class "Default")
      (node (ref "CONN1") (pin "P$23") (pinfunction "DISTRI_VBAT_P$23") (pintype "bidirectional"))
    )
    (net (code "81") (name "unconnected-(CONN1-DISTRI_VBAT-PadP$26)") (class "Default")
      (node (ref "CONN1") (pin "P$26") (pinfunction "DISTRI_VBAT_P$26") (pintype "bidirectional"))
    )
    (net (code "82") (name "unconnected-(CONN1-DISTRI_VBAT-PadP$28)") (class "Default")
      (node (ref "CONN1") (pin "P$28") (pinfunction "DISTRI_VBAT_P$28") (pintype "bidirectional"))
    )
    (net (code "83") (name "unconnected-(CONN1-DISTRI_VBAT-PadP$29)") (class "Default")
      (node (ref "CONN1") (pin "P$29") (pinfunction "DISTRI_VBAT_P$29") (pintype "bidirectional"))
    )
    (net (code "84") (name "unconnected-(CONN1-DISTRI_VBAT-PadP$31)") (class "Default")
      (node (ref "CONN1") (pin "P$31") (pinfunction "DISTRI_VBAT_P$31") (pintype "bidirectional"))
    )
    (net (code "85") (name "unconnected-(CONN1-ESTIMAT_3.3V-PadP$75)") (class "Default")
      (node (ref "CONN1") (pin "P$75") (pinfunction "ESTIMAT_3.3V_P$75") (pintype "bidirectional"))
    )
    (net (code "86") (name "unconnected-(CONN1-ESTIMAT_3.3V-PadP$76)") (class "Default")
      (node (ref "CONN1") (pin "P$76") (pinfunction "ESTIMAT_3.3V_P$76") (pintype "bidirectional"))
    )
    (net (code "87") (name "unconnected-(CONN1-ESTIMAT_5V-PadP$73)") (class "Default")
      (node (ref "CONN1") (pin "P$73") (pinfunction "ESTIMAT_5V_P$73") (pintype "bidirectional"))
    )
    (net (code "88") (name "unconnected-(CONN1-ESTIMAT_5V-PadP$74)") (class "Default")
      (node (ref "CONN1") (pin "P$74") (pinfunction "ESTIMAT_5V_P$74") (pintype "bidirectional"))
    )
    (net (code "89") (name "unconnected-(CONN1-ESTIMAT_GND-PadP$79)") (class "Default")
      (node (ref "CONN1") (pin "P$79") (pinfunction "ESTIMAT_GND_P$79") (pintype "bidirectional"))
    )
    (net (code "90") (name "unconnected-(CONN1-ESTIMAT_GND-PadP$80)") (class "Default")
      (node (ref "CONN1") (pin "P$80") (pinfunction "ESTIMAT_GND_P$80") (pintype "bidirectional"))
    )
    (net (code "91") (name "unconnected-(CONN1-ESTIMAT_VBAT-PadP$77)") (class "Default")
      (node (ref "CONN1") (pin "P$77") (pinfunction "ESTIMAT_VBAT_P$77") (pintype "bidirectional"))
    )
    (net (code "92") (name "unconnected-(CONN1-ESTIMAT_VBAT-PadP$78)") (class "Default")
      (node (ref "CONN1") (pin "P$78") (pinfunction "ESTIMAT_VBAT_P$78") (pintype "bidirectional"))
    )
    (net (code "93") (name "unconnected-(CONN1-MCU_GND-PadP$46)") (class "Default")
      (node (ref "CONN1") (pin "P$46") (pinfunction "MCU_GND_P$46") (pintype "bidirectional"))
    )
    (net (code "94") (name "unconnected-(CONN1-MCU_GND-PadP$47)") (class "Default")
      (node (ref "CONN1") (pin "P$47") (pinfunction "MCU_GND_P$47") (pintype "bidirectional"))
    )
    (net (code "95") (name "unconnected-(CONN1-MCU_GND-PadP$58)") (class "Default")
      (node (ref "CONN1") (pin "P$58") (pinfunction "MCU_GND_P$58") (pintype "bidirectional"))
    )
    (net (code "96") (name "unconnected-(CONN1-MCU_GND-PadP$59)") (class "Default")
      (node (ref "CONN1") (pin "P$59") (pinfunction "MCU_GND_P$59") (pintype "bidirectional"))
    )
    (net (code "97") (name "unconnected-(CONN1-PPT_GND-PadP$1)") (class "Default")
      (node (ref "CONN1") (pin "P$1") (pinfunction "PPT_GND_P$1") (pintype "bidirectional"))
    )
    (net (code "98") (name "unconnected-(CONN1-PPT_GND-PadP$3)") (class "Default")
      (node (ref "CONN1") (pin "P$3") (pinfunction "PPT_GND_P$3") (pintype "bidirectional"))
    )
    (net (code "99") (name "unconnected-(CONN1-PPT_GND-PadP$6)") (class "Default")
      (node (ref "CONN1") (pin "P$6") (pinfunction "PPT_GND_P$6") (pintype "bidirectional"))
    )
    (net (code "100") (name "unconnected-(CONN1-PPT_GND-PadP$8)") (class "Default")
      (node (ref "CONN1") (pin "P$8") (pinfunction "PPT_GND_P$8") (pintype "bidirectional"))
    )
    (net (code "101") (name "unconnected-(CONN1-PPT_GND-PadP$9)") (class "Default")
      (node (ref "CONN1") (pin "P$9") (pinfunction "PPT_GND_P$9") (pintype "bidirectional"))
    )
    (net (code "102") (name "unconnected-(CONN1-PPT_GND-PadP$11)") (class "Default")
      (node (ref "CONN1") (pin "P$11") (pinfunction "PPT_GND_P$11") (pintype "bidirectional"))
    )
    (net (code "103") (name "unconnected-(CONN1-PPT_GND-PadP$14)") (class "Default")
      (node (ref "CONN1") (pin "P$14") (pinfunction "PPT_GND_P$14") (pintype "bidirectional"))
    )
    (net (code "104") (name "unconnected-(CONN1-PPT_GND-PadP$16)") (class "Default")
      (node (ref "CONN1") (pin "P$16") (pinfunction "PPT_GND_P$16") (pintype "bidirectional"))
    )
    (net (code "105") (name "unconnected-(CONN1-PPT_VBAT-PadP$2)") (class "Default")
      (node (ref "CONN1") (pin "P$2") (pinfunction "PPT_VBAT_P$2") (pintype "bidirectional"))
    )
    (net (code "106") (name "unconnected-(CONN1-PPT_VBAT-PadP$4)") (class "Default")
      (node (ref "CONN1") (pin "P$4") (pinfunction "PPT_VBAT_P$4") (pintype "bidirectional"))
    )
    (net (code "107") (name "unconnected-(CONN1-PPT_VBAT-PadP$5)") (class "Default")
      (node (ref "CONN1") (pin "P$5") (pinfunction "PPT_VBAT_P$5") (pintype "bidirectional"))
    )
    (net (code "108") (name "unconnected-(CONN1-PPT_VBAT-PadP$7)") (class "Default")
      (node (ref "CONN1") (pin "P$7") (pinfunction "PPT_VBAT_P$7") (pintype "bidirectional"))
    )
    (net (code "109") (name "unconnected-(CONN1-PPT_VBAT-PadP$10)") (class "Default")
      (node (ref "CONN1") (pin "P$10") (pinfunction "PPT_VBAT_P$10") (pintype "bidirectional"))
    )
    (net (code "110") (name "unconnected-(CONN1-PPT_VBAT-PadP$12)") (class "Default")
      (node (ref "CONN1") (pin "P$12") (pinfunction "PPT_VBAT_P$12") (pintype "bidirectional"))
    )
    (net (code "111") (name "unconnected-(CONN1-PPT_VBAT-PadP$13)") (class "Default")
      (node (ref "CONN1") (pin "P$13") (pinfunction "PPT_VBAT_P$13") (pintype "bidirectional"))
    )
    (net (code "112") (name "unconnected-(CONN1-PPT_VBAT-PadP$15)") (class "Default")
      (node (ref "CONN1") (pin "P$15") (pinfunction "PPT_VBAT_P$15") (pintype "bidirectional"))
    )
    (net (code "113") (name "unconnected-(CONN1-PadP$33)") (class "Default")
      (node (ref "CONN1") (pin "P$33") (pinfunction "P$33_P$33") (pintype "bidirectional"))
    )
    (net (code "114") (name "unconnected-(CONN1-PadP$34)") (class "Default")
      (node (ref "CONN1") (pin "P$34") (pinfunction "P$34_P$34") (pintype "bidirectional"))
    )
    (net (code "115") (name "unconnected-(CONN1-PadP$35)") (class "Default")
      (node (ref "CONN1") (pin "P$35") (pinfunction "P$35_P$35") (pintype "bidirectional"))
    )
    (net (code "116") (name "unconnected-(CONN1-PadP$36)") (class "Default")
      (node (ref "CONN1") (pin "P$36") (pinfunction "P$36_P$36") (pintype "bidirectional"))
    )
    (net (code "117") (name "unconnected-(CONN1-PadP$37)") (class "Default")
      (node (ref "CONN1") (pin "P$37") (pinfunction "P$37_P$37") (pintype "bidirectional"))
    )
    (net (code "118") (name "unconnected-(CONN1-PadP$38)") (class "Default")
      (node (ref "CONN1") (pin "P$38") (pinfunction "P$38_P$38") (pintype "bidirectional"))
    )
    (net (code "119") (name "unconnected-(CONN1-PadP$39)") (class "Default")
      (node (ref "CONN1") (pin "P$39") (pinfunction "P$39_P$39") (pintype "bidirectional"))
    )
    (net (code "120") (name "unconnected-(CONN1-PadP$40)") (class "Default")
      (node (ref "CONN1") (pin "P$40") (pinfunction "P$40_P$40") (pintype "bidirectional"))
    )
    (net (code "121") (name "unconnected-(CONN1-PadP$41)") (class "Default")
      (node (ref "CONN1") (pin "P$41") (pinfunction "P$41_P$41") (pintype "bidirectional"))
    )
    (net (code "122") (name "unconnected-(CONN1-PadP$42)") (class "Default")
      (node (ref "CONN1") (pin "P$42") (pinfunction "P$42_P$42") (pintype "bidirectional"))
    )
    (net (code "123") (name "unconnected-(CONN1-PadP$43)") (class "Default")
      (node (ref "CONN1") (pin "P$43") (pinfunction "P$43_P$43") (pintype "bidirectional"))
    )
    (net (code "124") (name "unconnected-(CONN1-PadP$44)") (class "Default")
      (node (ref "CONN1") (pin "P$44") (pinfunction "P$44_P$44") (pintype "bidirectional"))
    )
    (net (code "125") (name "unconnected-(CONN1-PadP$48)") (class "Default")
      (node (ref "CONN1") (pin "P$48") (pinfunction "P$48_P$48") (pintype "bidirectional"))
    )
    (net (code "126") (name "unconnected-(CONN1-PadP$52)") (class "Default")
      (node (ref "CONN1") (pin "P$52") (pinfunction "P$52_P$52") (pintype "bidirectional"))
    )
    (net (code "127") (name "unconnected-(CONN1-PadP$56)") (class "Default")
      (node (ref "CONN1") (pin "P$56") (pinfunction "P$56_P$56") (pintype "bidirectional"))
    )
    (net (code "128") (name "unconnected-(CONN1-PadP$60)") (class "Default")
      (node (ref "CONN1") (pin "P$60") (pinfunction "P$60_P$60") (pintype "bidirectional"))
    )
    (net (code "129") (name "unconnected-(CONN1-PadP$61)") (class "Default")
      (node (ref "CONN1") (pin "P$61") (pinfunction "P$61_P$61") (pintype "bidirectional"))
    )
    (net (code "130") (name "unconnected-(CONN1-PadP$62)") (class "Default")
      (node (ref "CONN1") (pin "P$62") (pinfunction "P$62_P$62") (pintype "bidirectional"))
    )
    (net (code "131") (name "unconnected-(CONN1-PadP$63)") (class "Default")
      (node (ref "CONN1") (pin "P$63") (pinfunction "P$63_P$63") (pintype "bidirectional"))
    )
    (net (code "132") (name "unconnected-(CONN1-PadP$64)") (class "Default")
      (node (ref "CONN1") (pin "P$64") (pinfunction "P$64_P$64") (pintype "bidirectional"))
    )
    (net (code "133") (name "unconnected-(CONN1-PadP$65)") (class "Default")
      (node (ref "CONN1") (pin "P$65") (pinfunction "P$65_P$65") (pintype "bidirectional"))
    )
    (net (code "134") (name "unconnected-(CONN1-PadP$66)") (class "Default")
      (node (ref "CONN1") (pin "P$66") (pinfunction "P$66_P$66") (pintype "bidirectional"))
    )
    (net (code "135") (name "unconnected-(CONN1-PadP$67)") (class "Default")
      (node (ref "CONN1") (pin "P$67") (pinfunction "P$67_P$67") (pintype "bidirectional"))
    )
    (net (code "136") (name "unconnected-(CONN1-PadP$68)") (class "Default")
      (node (ref "CONN1") (pin "P$68") (pinfunction "P$68_P$68") (pintype "bidirectional"))
    )
    (net (code "137") (name "unconnected-(CONN1-PadP$89)") (class "Default")
      (node (ref "CONN1") (pin "P$89") (pinfunction "P$89_P$89") (pintype "bidirectional"))
    )
    (net (code "138") (name "unconnected-(CONN1-PadP$90)") (class "Default")
      (node (ref "CONN1") (pin "P$90") (pinfunction "P$90_P$90") (pintype "bidirectional"))
    )
    (net (code "139") (name "unconnected-(CONN1-PadP$91)") (class "Default")
      (node (ref "CONN1") (pin "P$91") (pinfunction "P$91_P$91") (pintype "bidirectional"))
    )
    (net (code "140") (name "unconnected-(CONN1-PadP$92)") (class "Default")
      (node (ref "CONN1") (pin "P$92") (pinfunction "P$92_P$92") (pintype "bidirectional"))
    )
    (net (code "141") (name "unconnected-(CONN1-PadP$95)") (class "Default")
      (node (ref "CONN1") (pin "P$95") (pinfunction "P$95_P$95") (pintype "bidirectional"))
    )
    (net (code "142") (name "unconnected-(CONN1-PadP$96)") (class "Default")
      (node (ref "CONN1") (pin "P$96") (pinfunction "P$96_P$96") (pintype "bidirectional"))
    )
    (net (code "143") (name "unconnected-(CONN1-RAHS_GND-PadP$94)") (class "Default")
      (node (ref "CONN1") (pin "P$94") (pinfunction "RAHS_GND_P$94") (pintype "bidirectional"))
    )
    (net (code "144") (name "unconnected-(CONN1-RAHS_VBAT-PadP$93)") (class "Default")
      (node (ref "CONN1") (pin "P$93") (pinfunction "RAHS_VBAT_P$93") (pintype "bidirectional"))
    )
    (net (code "145") (name "unconnected-(CONN1-WHEEL_GND-PadP$71)") (class "Default")
      (node (ref "CONN1") (pin "P$71") (pinfunction "WHEEL_GND_P$71") (pintype "bidirectional"))
    )
    (net (code "146") (name "unconnected-(CONN1-WHEEL_GND-PadP$72)") (class "Default")
      (node (ref "CONN1") (pin "P$72") (pinfunction "WHEEL_GND_P$72") (pintype "bidirectional"))
    )
    (net (code "147") (name "unconnected-(CONN1-WHEEL_VBATT-PadP$69)") (class "Default")
      (node (ref "CONN1") (pin "P$69") (pinfunction "WHEEL_VBATT_P$69") (pintype "bidirectional"))
    )
    (net (code "148") (name "unconnected-(CONN1-WHEEL_VBATT-PadP$70)") (class "Default")
      (node (ref "CONN1") (pin "P$70") (pinfunction "WHEEL_VBATT_P$70") (pintype "bidirectional"))
    )
    (net (code "149") (name "unconnected-(U3-EVENT1{slash}TXD3-PadP$9)") (class "Default")
      (node (ref "U3") (pin "P$9") (pinfunction "EVENT1/TXD3_P$9") (pintype "bidirectional"))
    )
    (net (code "150") (name "unconnected-(U3-EVENT2{slash}CAN1TX-PadP$7)") (class "Default")
      (node (ref "U3") (pin "P$7") (pinfunction "EVENT2/CAN1TX_P$7") (pintype "bidirectional"))
    )
    (net (code "151") (name "unconnected-(U3-NC-PadP$1)") (class "Default")
      (node (ref "U3") (pin "P$1") (pinfunction "NC_P$1") (pintype "bidirectional"))
    )
    (net (code "152") (name "unconnected-(U3-RXD1-PadP$12)") (class "Default")
      (node (ref "U3") (pin "P$12") (pinfunction "RXD1_P$12") (pintype "bidirectional"))
    )
    (net (code "153") (name "unconnected-(U3-TXD1-PadP$11)") (class "Default")
      (node (ref "U3") (pin "P$11") (pinfunction "TXD1_P$11") (pintype "bidirectional"))
    )
    (net (code "154") (name "unconnected-(U3-VARF{slash}CAN1RX-PadP$6)") (class "Default")
      (node (ref "U3") (pin "P$6") (pinfunction "VARF/CAN1RX_P$6") (pintype "bidirectional"))
    )
  )
)
